# Blynk_Watering_System_main.net
KiCad netlist of a schematic drawn in EAGLE
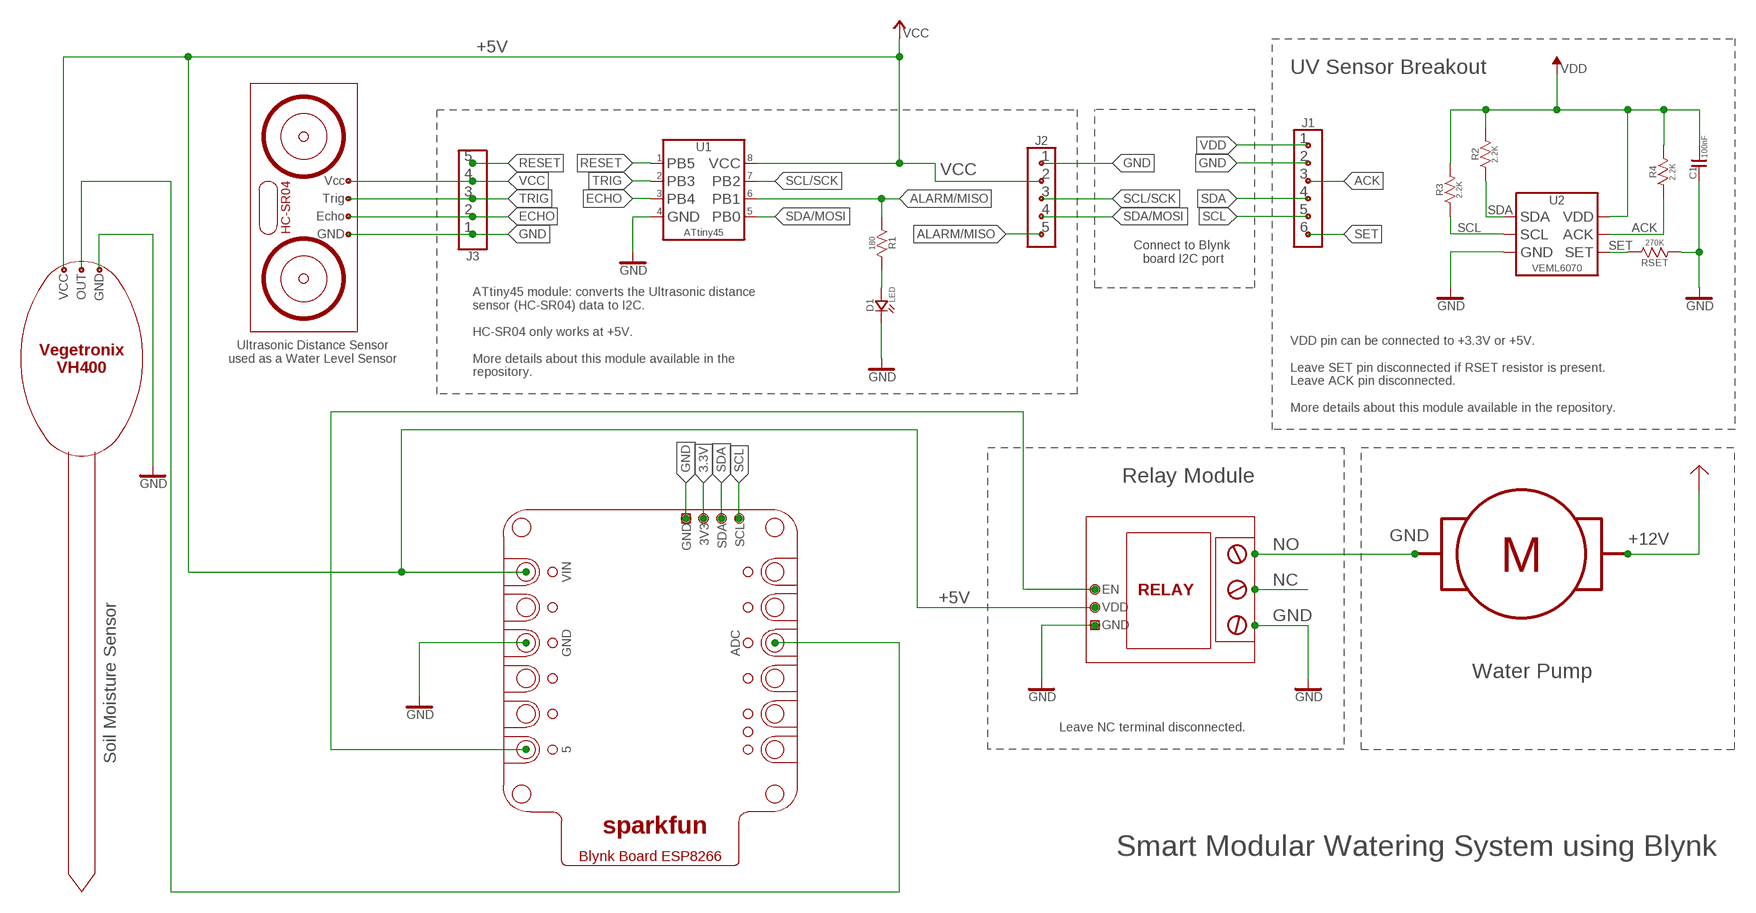
[diagram p0: schematic, sheet 1]

(export (version "E")
  (design (tool "Eeschema 10.0.6"))
  (components
    (comp (ref "C1")
      (value "100nF")
      (footprint "eagle-import:0603[1608]")
      (libsource (lib "eagle-import") (part "CAPACITOR_0603[1608]"))
    )
    (comp (ref "D1")
      (value "LED")
      (footprint "eagle-import:0805[2012]")
      (libsource (lib "eagle-import") (part "LED_0805[2012]"))
    )
    (comp (ref "J1")
      (value "PIN_HEADER_1X06_0.1\"_STR_G[2]_PTH")
      (footprint "eagle-import:PIN_HEADER_1X06_0.1__STR_G[2]_PTH")
      (libsource (lib "eagle-import") (part "PIN_HEADER_1X06_0.1{dblquote}_STR_G[2]_PTH"))
    )
    (comp (ref "J2")
      (value "PIN_HEADER_1X05_0.1\"_STR_G[1]_PTH")
      (footprint "eagle-import:PIN_HEADER_1X05_0.1__STR_G[1]_PTH")
      (libsource (lib "eagle-import") (part "PIN_HEADER_1X05_0.1{dblquote}_STR_G[1]_PTH"))
    )
    (comp (ref "J3")
      (value "PIN_HEADER_1X05_0.1\"_STR_G[1]_PTH")
      (footprint "eagle-import:PIN_HEADER_1X05_0.1__STR_G[1]_PTH")
      (libsource (lib "eagle-import") (part "PIN_HEADER_1X05_0.1{dblquote}_STR_G[1]_PTH"))
    )
    (comp (ref "R1")
      (value "180")
      (footprint "eagle-import:0603[1608]")
      (libsource (lib "eagle-import") (part "RESISTOR_0603[1008]"))
    )
    (comp (ref "R2")
      (value "2.2K")
      (footprint "eagle-import:0603[1608]")
      (libsource (lib "eagle-import") (part "RESISTOR_0603[1008]"))
    )
    (comp (ref "R3")
      (value "2.2K")
      (footprint "eagle-import:0603[1608]")
      (libsource (lib "eagle-import") (part "RESISTOR_0603[1008]"))
    )
    (comp (ref "R4")
      (value "2.2K")
      (footprint "eagle-import:0603[1608]")
      (libsource (lib "eagle-import") (part "RESISTOR_0603[1008]"))
    )
    (comp (ref "RSET")
      (value "270K")
      (footprint "eagle-import:0603[1608]")
      (libsource (lib "eagle-import") (part "RESISTOR_0603[1008]"))
    )
    (comp (ref "U1")
      (value "ATtiny45")
      (footprint "eagle-import:TSSOP_MO-153-AC")
      (libsource (lib "eagle-import") (part "ATTINY25/45/85_TSSOP_MO-153-AC"))
    )
    (comp (ref "U2")
      (value "VEML6070")
      (footprint "eagle-import:OPLGA")
      (libsource (lib "eagle-import") (part "UV_LIGHT_SENSOR_I2C_OPLGA"))
    )
  )
  (nets
    (net (code "5") (name "ACK") (class "Default")
      (node (ref "J1") (pin "3") (pinfunction "3_3") (pintype "bidirectional"))
      (node (ref "R4") (pin "1") (pinfunction "P1_1") (pintype "passive"))
      (node (ref "U2") (pin "2") (pinfunction "ACK_2") (pintype "bidirectional"))
    )
    (net (code "6") (name "ALARM{slash}MISO") (class "Default")
      (node (ref "J2") (pin "5") (pinfunction "5_5") (pintype "bidirectional"))
      (node (ref "R1") (pin "1") (pinfunction "P1_1") (pintype "passive"))
      (node (ref "U1") (pin "6") (pinfunction "PB1_6") (pintype "input"))
    )
    (net (code "7") (name "ECHO") (class "Default")
      (node (ref "J3") (pin "2") (pinfunction "2_2") (pintype "bidirectional"))
      (node (ref "U1") (pin "3") (pinfunction "PB4_3") (pintype "bidirectional"))
    )
    (net (code "8") (name "GND") (class "Default")
      (node (ref "C1") (pin "1") (pinfunction "1_1") (pintype "passive"))
      (node (ref "D1") (pin "-") (pinfunction "-_-") (pintype "bidirectional"))
      (node (ref "J1") (pin "2") (pinfunction "2_2") (pintype "bidirectional"))
      (node (ref "J2") (pin "1") (pinfunction "1_1") (pintype "bidirectional"))
      (node (ref "J3") (pin "1") (pinfunction "1_1") (pintype "bidirectional"))
      (node (ref "RSET") (pin "1") (pinfunction "P1_1") (pintype "passive"))
      (node (ref "U1") (pin "4") (pinfunction "GND_4") (pintype "power_in"))
      (node (ref "U2") (pin "1") (pinfunction "GND_1") (pintype "input"))
    )
    (net (code "9") (name "Net-(R1-P2)") (class "Default")
      (node (ref "D1") (pin "+") (pinfunction "+_+") (pintype "bidirectional"))
      (node (ref "R1") (pin "2") (pinfunction "P2_2") (pintype "passive"))
    )
    (net (code "10") (name "RESET") (class "Default")
      (node (ref "J3") (pin "5") (pinfunction "5_5") (pintype "bidirectional"))
      (node (ref "U1") (pin "1") (pinfunction "PB5_1") (pintype "input"))
    )
    (net (code "11") (name "SCL") (class "Default")
      (node (ref "J1") (pin "5") (pinfunction "5_5") (pintype "bidirectional"))
      (node (ref "R3") (pin "1") (pinfunction "P1_1") (pintype "passive"))
      (node (ref "U2") (pin "5") (pinfunction "SCL_5") (pintype "input"))
    )
    (net (code "12") (name "SCL{slash}SCK") (class "Default")
      (node (ref "J2") (pin "3") (pinfunction "3_3") (pintype "bidirectional"))
      (node (ref "U1") (pin "7") (pinfunction "PB2_7") (pintype "input"))
    )
    (net (code "13") (name "SDA") (class "Default")
      (node (ref "J1") (pin "4") (pinfunction "4_4") (pintype "bidirectional"))
      (node (ref "R2") (pin "1") (pinfunction "P1_1") (pintype "passive"))
      (node (ref "U2") (pin "3") (pinfunction "SDA_3") (pintype "bidirectional"))
    )
    (net (code "14") (name "SDA{slash}MOSI") (class "Default")
      (node (ref "J2") (pin "4") (pinfunction "4_4") (pintype "bidirectional"))
      (node (ref "U1") (pin "5") (pinfunction "PB0_5") (pintype "input"))
    )
    (net (code "15") (name "SET") (class "Default")
      (node (ref "J1") (pin "6") (pinfunction "6_6") (pintype "bidirectional"))
      (node (ref "RSET") (pin "2") (pinfunction "P2_2") (pintype "passive"))
      (node (ref "U2") (pin "4") (pinfunction "SET_4") (pintype "input"))
    )
    (net (code "16") (name "TRIG") (class "Default")
      (node (ref "J3") (pin "3") (pinfunction "3_3") (pintype "bidirectional"))
      (node (ref "U1") (pin "2") (pinfunction "PB3_2") (pintype "bidirectional"))
    )
    (net (code "17") (name "VCC") (class "Default")
      (node (ref "J2") (pin "2") (pinfunction "2_2") (pintype "bidirectional"))
      (node (ref "J3") (pin "4") (pinfunction "4_4") (pintype "bidirectional"))
      (node (ref "U1") (pin "8") (pinfunction "VCC_8") (pintype "power_in"))
    )
    (net (code "18") (name "VDD") (class "Default")
      (node (ref "C1") (pin "2") (pinfunction "2_2") (pintype "passive"))
      (node (ref "J1") (pin "1") (pinfunction "1_1") (pintype "bidirectional"))
      (node (ref "R2") (pin "2") (pinfunction "P2_2") (pintype "passive"))
      (node (ref "R3") (pin "2") (pinfunction "P2_2") (pintype "passive"))
      (node (ref "R4") (pin "2") (pinfunction "P2_2") (pintype "passive"))
      (node (ref "U2") (pin "6") (pinfunction "VDD_6") (pintype "power_in"))
    )
  )
)
